# Avionicapart1.net
KiCad netlist of a schematic drawn in EAGLE
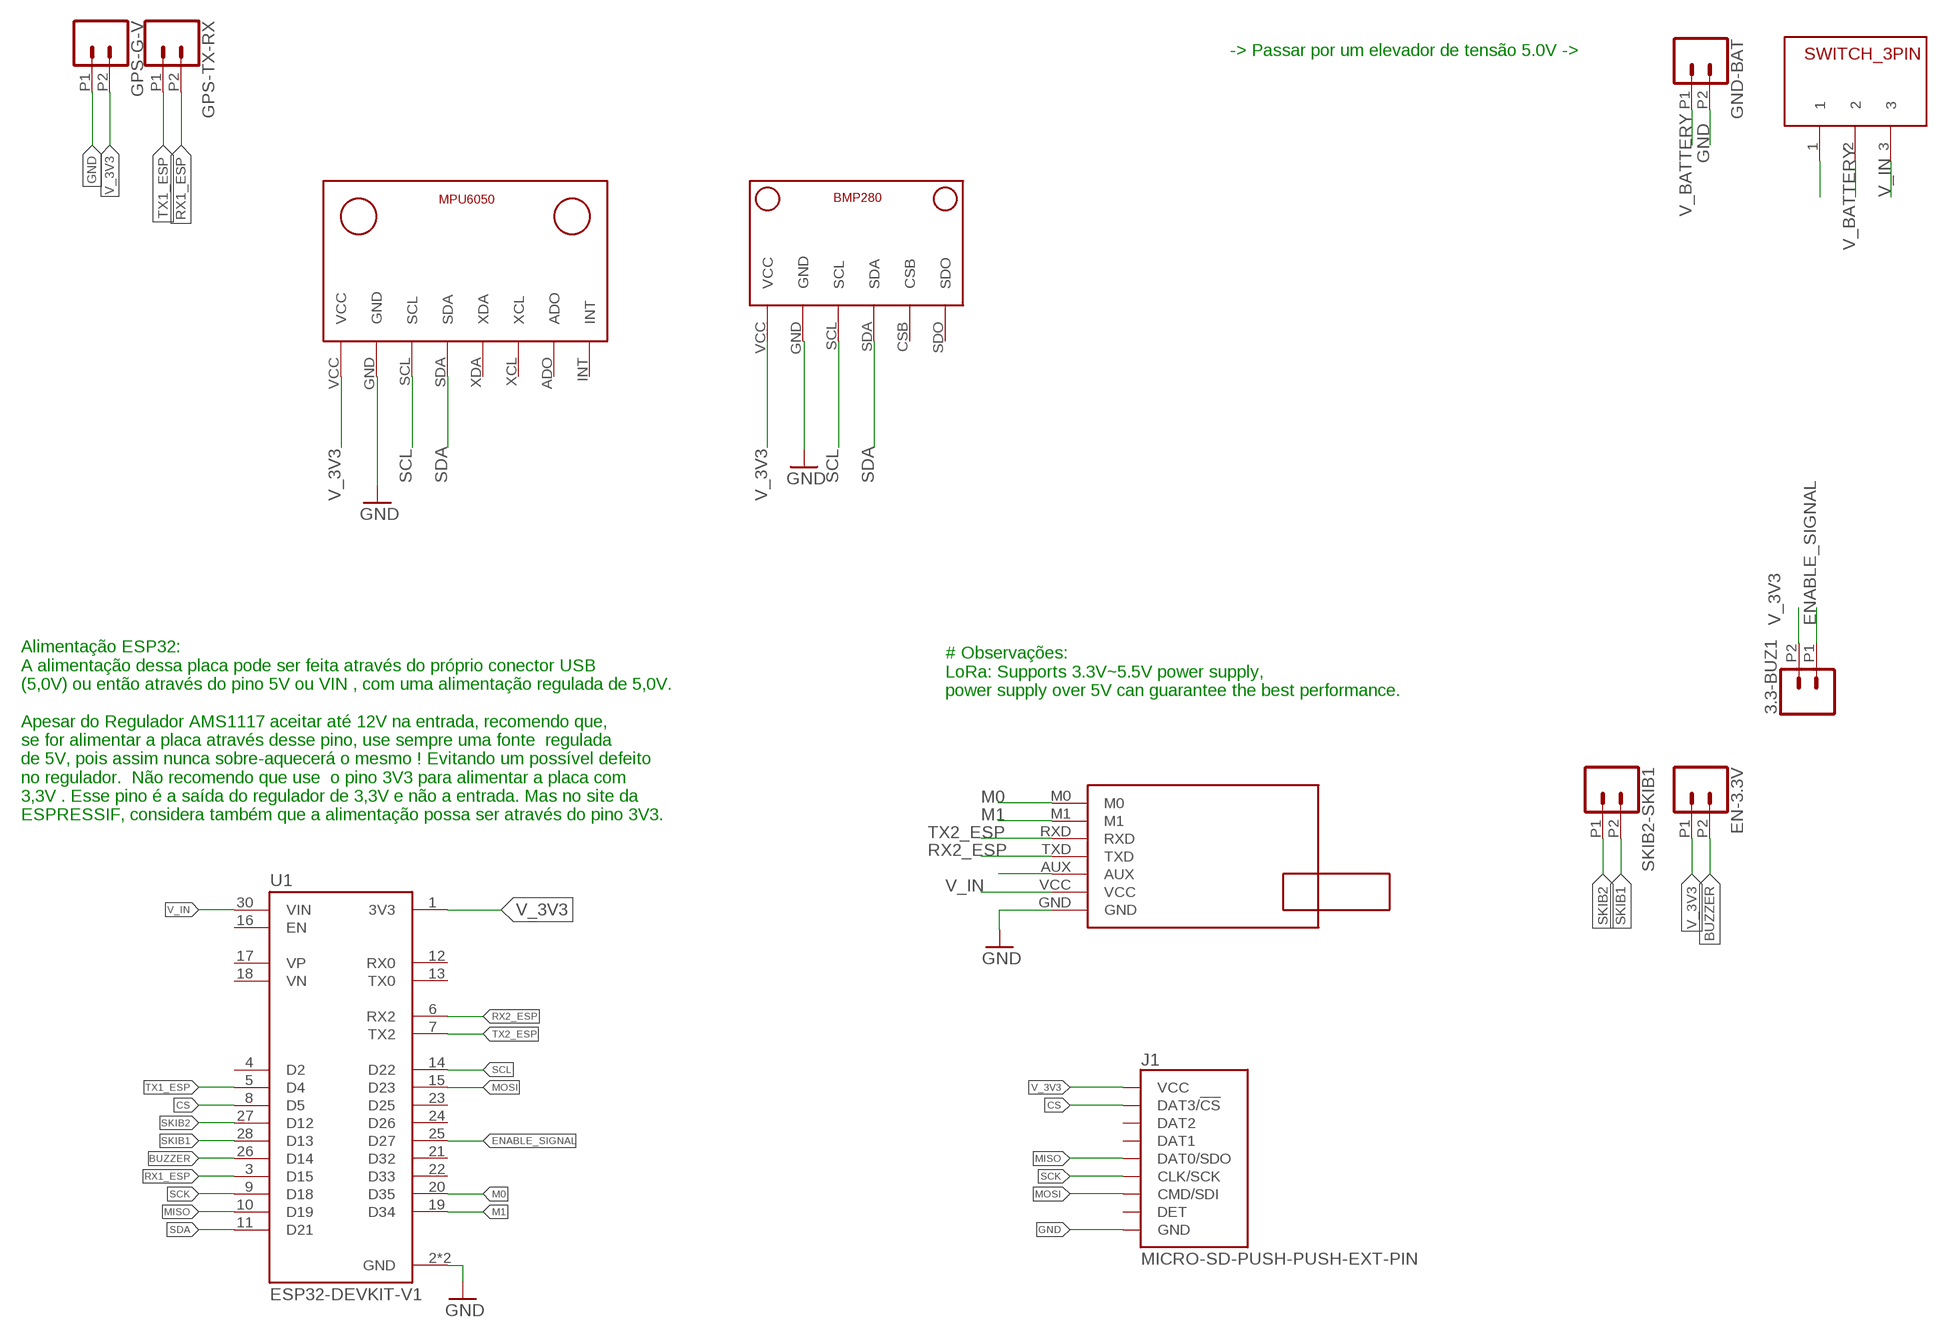
[diagram p0: schematic, sheet 1]

(export (version "E")
  (design (tool "Eeschema 10.0.6"))
  (components
    (comp (ref "3.3-BUZ1")
      (value "CONN_022.54MM_SCREWTERM")
      (footprint "eagle-import:1X02_2.54_SCREWTERM")
      (libsource (lib "eagle-import") (part "CONN_022.54MM_SCREWTERM"))
    )
    (comp (ref "EN-3.3V")
      (value "CONN_022.54MM_SCREWTERM")
      (footprint "eagle-import:1X02_2.54_SCREWTERM")
      (libsource (lib "eagle-import") (part "CONN_022.54MM_SCREWTERM"))
    )
    (comp (ref "GND-BAT")
      (value "CONN_022.54MM_SCREWTERM")
      (footprint "eagle-import:1X02_2.54_SCREWTERM")
      (libsource (lib "eagle-import") (part "CONN_022.54MM_SCREWTERM"))
    )
    (comp (ref "GPS-G-V")
      (value "CONN_022.54MM_SCREWTERM")
      (footprint "eagle-import:1X02_2.54_SCREWTERM")
      (libsource (lib "eagle-import") (part "CONN_022.54MM_SCREWTERM"))
    )
    (comp (ref "GPS-TX-RX")
      (value "CONN_022.54MM_SCREWTERM")
      (footprint "eagle-import:1X02_2.54_SCREWTERM")
      (libsource (lib "eagle-import") (part "CONN_022.54MM_SCREWTERM"))
    )
    (comp (ref "J1")
      (value "MICRO-SD-PUSH-PUSH-EXT-PIN")
      (footprint "eagle-import:MICROSD-EXTERNALPIN")
      (libsource (lib "eagle-import") (part "MICRO-SD-PUSH-PUSH-EXT-PIN"))
    )
    (comp (ref "SKIB2-SKIB1")
      (value "CONN_022.54MM_SCREWTERM")
      (footprint "eagle-import:1X02_2.54_SCREWTERM")
      (libsource (lib "eagle-import") (part "CONN_022.54MM_SCREWTERM"))
    )
    (comp (ref "U$2")
      (value "E22-400T30D")
      (footprint "eagle-import:E22-400T30D_FOOTPRINT")
      (libsource (lib "eagle-import") (part "E22-400T30D"))
    )
    (comp (ref "U$4")
      (value "BMP280V1")
      (footprint "eagle-import:BMP280_FOOTPRINT")
      (libsource (lib "eagle-import") (part "BMP280V1"))
    )
    (comp (ref "U$6")
      (value "MPU6050V1")
      (footprint "eagle-import:MPU6050_FOOTPRINT")
      (libsource (lib "eagle-import") (part "MPU6050V1"))
    )
    (comp (ref "U$11")
      (value "SWITCH_3PIN")
      (footprint "eagle-import:SWITCH_3PIN")
      (libsource (lib "eagle-import") (part "SWITCH_3PIN"))
    )
    (comp (ref "U1")
      (value "ESP32-DEVKIT-V1")
      (footprint "eagle-import:MODULE_ESP32_DEVKIT_V1")
      (fields (field (name "MF") "Do it"))
      (libsource (lib "eagle-import") (part "ESP32-DEVKIT-V1"))
    )
  )
  (nets
    (net (code "1") (name "/V_BATTERY") (class "Default")
      (node (ref "GND-BAT") (pin "P1") (pinfunction "1_P1") (pintype "passive"))
      (node (ref "U$11") (pin "2") (pinfunction "2_2") (pintype "bidirectional"))
    )
    (net (code "2") (name "BUZZER") (class "Default")
      (node (ref "EN-3.3V") (pin "P2") (pinfunction "2_P2") (pintype "passive"))
      (node (ref "U1") (pin "26") (pinfunction "D14_26") (pintype "bidirectional"))
    )
    (net (code "3") (name "CS") (class "Default")
      (node (ref "J1") (pin "2") (pinfunction "DAT3/~{CS}_2") (pintype "bidirectional"))
      (node (ref "U1") (pin "8") (pinfunction "D5_8") (pintype "bidirectional"))
    )
    (net (code "4") (name "ENABLE_SIGNAL") (class "Default")
      (node (ref "3.3-BUZ1") (pin "P1") (pinfunction "1_P1") (pintype "passive"))
      (node (ref "U1") (pin "25") (pinfunction "D27_25") (pintype "bidirectional"))
    )
    (net (code "5") (name "GND") (class "Default")
      (node (ref "GND-BAT") (pin "P2") (pinfunction "2_P2") (pintype "passive"))
      (node (ref "GPS-G-V") (pin "P1") (pinfunction "1_P1") (pintype "passive"))
      (node (ref "J1") (pin "10") (pinfunction "GND_10") (pintype "bidirectional"))
      (node (ref "J1") (pin "11") (pinfunction "GND_11") (pintype "bidirectional"))
      (node (ref "J1") (pin "12") (pinfunction "GND_12") (pintype "bidirectional"))
      (node (ref "J1") (pin "13") (pinfunction "GND_13") (pintype "bidirectional"))
      (node (ref "J1") (pin "6") (pinfunction "GND_6") (pintype "bidirectional"))
      (node (ref "U$2") (pin "GND") (pinfunction "GND_GND") (pintype "bidirectional"))
      (node (ref "U$4") (pin "GND") (pinfunction "GND_GND") (pintype "bidirectional"))
      (node (ref "U$6") (pin "GND") (pinfunction "GND_GND") (pintype "bidirectional"))
      (node (ref "U1") (pin "2") (pinfunction "GND_2") (pintype "power_in"))
      (node (ref "U1") (pin "29") (pinfunction "GND_29") (pintype "power_in"))
    )
    (net (code "6") (name "M0") (class "Default")
      (node (ref "U$2") (pin "M0") (pinfunction "M0_M0") (pintype "bidirectional"))
      (node (ref "U1") (pin "20") (pinfunction "D35_20") (pintype "bidirectional"))
    )
    (net (code "7") (name "M1") (class "Default")
      (node (ref "U$2") (pin "M1") (pinfunction "M1_M1") (pintype "bidirectional"))
      (node (ref "U1") (pin "19") (pinfunction "D34_19") (pintype "bidirectional"))
    )
    (net (code "8") (name "MISO") (class "Default")
      (node (ref "J1") (pin "7") (pinfunction "DAT0/SDO_7") (pintype "bidirectional"))
      (node (ref "U1") (pin "10") (pinfunction "D19_10") (pintype "bidirectional"))
    )
    (net (code "9") (name "MOSI") (class "Default")
      (node (ref "J1") (pin "3") (pinfunction "CMD/SDI_3") (pintype "bidirectional"))
      (node (ref "U1") (pin "15") (pinfunction "D23_15") (pintype "bidirectional"))
    )
    (net (code "10") (name "RX1_ESP") (class "Default")
      (node (ref "GPS-TX-RX") (pin "P2") (pinfunction "2_P2") (pintype "passive"))
      (node (ref "U1") (pin "3") (pinfunction "D15_3") (pintype "bidirectional"))
    )
    (net (code "11") (name "RX2_ESP") (class "Default")
      (node (ref "U$2") (pin "TXD") (pinfunction "TXD_TXD") (pintype "bidirectional"))
      (node (ref "U1") (pin "6") (pinfunction "RX2_6") (pintype "input"))
    )
    (net (code "12") (name "SCK") (class "Default")
      (node (ref "J1") (pin "5") (pinfunction "CLK/SCK_5") (pintype "bidirectional"))
      (node (ref "U1") (pin "9") (pinfunction "D18_9") (pintype "bidirectional"))
    )
    (net (code "13") (name "SCL") (class "Default")
      (node (ref "U$4") (pin "SCL") (pinfunction "SCL_SCL") (pintype "bidirectional"))
      (node (ref "U$6") (pin "SCL") (pinfunction "SCL_SCL") (pintype "bidirectional"))
      (node (ref "U1") (pin "14") (pinfunction "D22_14") (pintype "bidirectional"))
    )
    (net (code "14") (name "SDA") (class "Default")
      (node (ref "U$4") (pin "SDA") (pinfunction "SDA_SDA") (pintype "bidirectional"))
      (node (ref "U$6") (pin "SDA") (pinfunction "SDA_SDA") (pintype "bidirectional"))
      (node (ref "U1") (pin "11") (pinfunction "D21_11") (pintype "bidirectional"))
    )
    (net (code "15") (name "SKIB1") (class "Default")
      (node (ref "SKIB2-SKIB1") (pin "P2") (pinfunction "2_P2") (pintype "passive"))
      (node (ref "U1") (pin "28") (pinfunction "D13_28") (pintype "bidirectional"))
    )
    (net (code "16") (name "SKIB2") (class "Default")
      (node (ref "SKIB2-SKIB1") (pin "P1") (pinfunction "1_P1") (pintype "passive"))
      (node (ref "U1") (pin "27") (pinfunction "D12_27") (pintype "bidirectional"))
    )
    (net (code "17") (name "TX1_ESP") (class "Default")
      (node (ref "GPS-TX-RX") (pin "P1") (pinfunction "1_P1") (pintype "passive"))
      (node (ref "U1") (pin "5") (pinfunction "D4_5") (pintype "bidirectional"))
    )
    (net (code "18") (name "TX2_ESP") (class "Default")
      (node (ref "U$2") (pin "RXD") (pinfunction "RXD_RXD") (pintype "bidirectional"))
      (node (ref "U1") (pin "7") (pinfunction "TX2_7") (pintype "output"))
    )
    (net (code "19") (name "V_3V3") (class "Default")
      (node (ref "3.3-BUZ1") (pin "P2") (pinfunction "2_P2") (pintype "passive"))
      (node (ref "EN-3.3V") (pin "P1") (pinfunction "1_P1") (pintype "passive"))
      (node (ref "GPS-G-V") (pin "P2") (pinfunction "2_P2") (pintype "passive"))
      (node (ref "J1") (pin "4") (pinfunction "VCC_4") (pintype "bidirectional"))
      (node (ref "U$4") (pin "VCC") (pinfunction "VCC_VCC") (pintype "bidirectional"))
      (node (ref "U$6") (pin "VCC") (pinfunction "VCC_VCC") (pintype "bidirectional"))
      (node (ref "U1") (pin "1") (pinfunction "3V3_1") (pintype "output"))
    )
    (net (code "20") (name "V_IN") (class "Default")
      (node (ref "U$11") (pin "3") (pinfunction "3_3") (pintype "bidirectional"))
      (node (ref "U$2") (pin "VCC") (pinfunction "VCC_VCC") (pintype "bidirectional"))
      (node (ref "U1") (pin "30") (pinfunction "VIN_30") (pintype "input"))
    )
    (net (code "21") (name "unconnected-(J1-DAT1-Pad8)") (class "Default")
      (node (ref "J1") (pin "8") (pinfunction "DAT1_8") (pintype "bidirectional"))
    )
    (net (code "22") (name "unconnected-(J1-DAT2-Pad1)") (class "Default")
      (node (ref "J1") (pin "1") (pinfunction "DAT2_1") (pintype "bidirectional"))
    )
    (net (code "23") (name "unconnected-(J1-DET-Pad9)") (class "Default")
      (node (ref "J1") (pin "9") (pinfunction "DET_9") (pintype "bidirectional"))
    )
    (net (code "24") (name "unconnected-(U$2-PadAUX)") (class "Default")
      (node (ref "U$2") (pin "AUX") (pinfunction "AUX_AUX") (pintype "bidirectional"))
    )
    (net (code "25") (name "unconnected-(U$4-PadCSB)") (class "Default")
      (node (ref "U$4") (pin "CSB") (pinfunction "CSB_CSB") (pintype "bidirectional"))
    )
    (net (code "26") (name "unconnected-(U$4-PadSDO)") (class "Default")
      (node (ref "U$4") (pin "SDO") (pinfunction "SDO_SDO") (pintype "bidirectional"))
    )
    (net (code "27") (name "unconnected-(U$6-PadADO)") (class "Default")
      (node (ref "U$6") (pin "ADO") (pinfunction "ADO_ADO") (pintype "bidirectional"))
    )
    (net (code "28") (name "unconnected-(U$6-PadINT)") (class "Default")
      (node (ref "U$6") (pin "INT") (pinfunction "INT_INT") (pintype "bidirectional"))
    )
    (net (code "29") (name "unconnected-(U$6-PadXCL)") (class "Default")
      (node (ref "U$6") (pin "XCL") (pinfunction "XCL_XCL") (pintype "bidirectional"))
    )
    (net (code "30") (name "unconnected-(U$6-PadXDA)") (class "Default")
      (node (ref "U$6") (pin "XDA") (pinfunction "XDA_XDA") (pintype "bidirectional"))
    )
    (net (code "31") (name "unconnected-(U$11-Pad1)") (class "Default")
      (node (ref "U$11") (pin "1") (pinfunction "1_1") (pintype "bidirectional"))
    )
    (net (code "32") (name "unconnected-(U1-D2-Pad4)") (class "Default")
      (node (ref "U1") (pin "4") (pinfunction "D2_4") (pintype "bidirectional"))
    )
    (net (code "33") (name "unconnected-(U1-D25-Pad23)") (class "Default")
      (node (ref "U1") (pin "23") (pinfunction "D25_23") (pintype "bidirectional"))
    )
    (net (code "34") (name "unconnected-(U1-D26-Pad24)") (class "Default")
      (node (ref "U1") (pin "24") (pinfunction "D26_24") (pintype "bidirectional"))
    )
    (net (code "35") (name "unconnected-(U1-D32-Pad21)") (class "Default")
      (node (ref "U1") (pin "21") (pinfunction "D32_21") (pintype "bidirectional"))
    )
    (net (code "36") (name "unconnected-(U1-D33-Pad22)") (class "Default")
      (node (ref "U1") (pin "22") (pinfunction "D33_22") (pintype "bidirectional"))
    )
    (net (code "37") (name "unconnected-(U1-EN-Pad16)") (class "Default")
      (node (ref "U1") (pin "16") (pinfunction "EN_16") (pintype "input"))
    )
    (net (code "38") (name "unconnected-(U1-RX0-Pad12)") (class "Default")
      (node (ref "U1") (pin "12") (pinfunction "RX0_12") (pintype "input"))
    )
    (net (code "39") (name "unconnected-(U1-TX0-Pad13)") (class "Default")
      (node (ref "U1") (pin "13") (pinfunction "TX0_13") (pintype "output"))
    )
    (net (code "40") (name "unconnected-(U1-VN-Pad18)") (class "Default")
      (node (ref "U1") (pin "18") (pinfunction "VN_18") (pintype "bidirectional"))
    )
    (net (code "41") (name "unconnected-(U1-VP-Pad17)") (class "Default")
      (node (ref "U1") (pin "17") (pinfunction "VP_17") (pintype "bidirectional"))
    )
  )
)
